# RH001_1.net
KiCad netlist of a schematic drawn in EAGLE
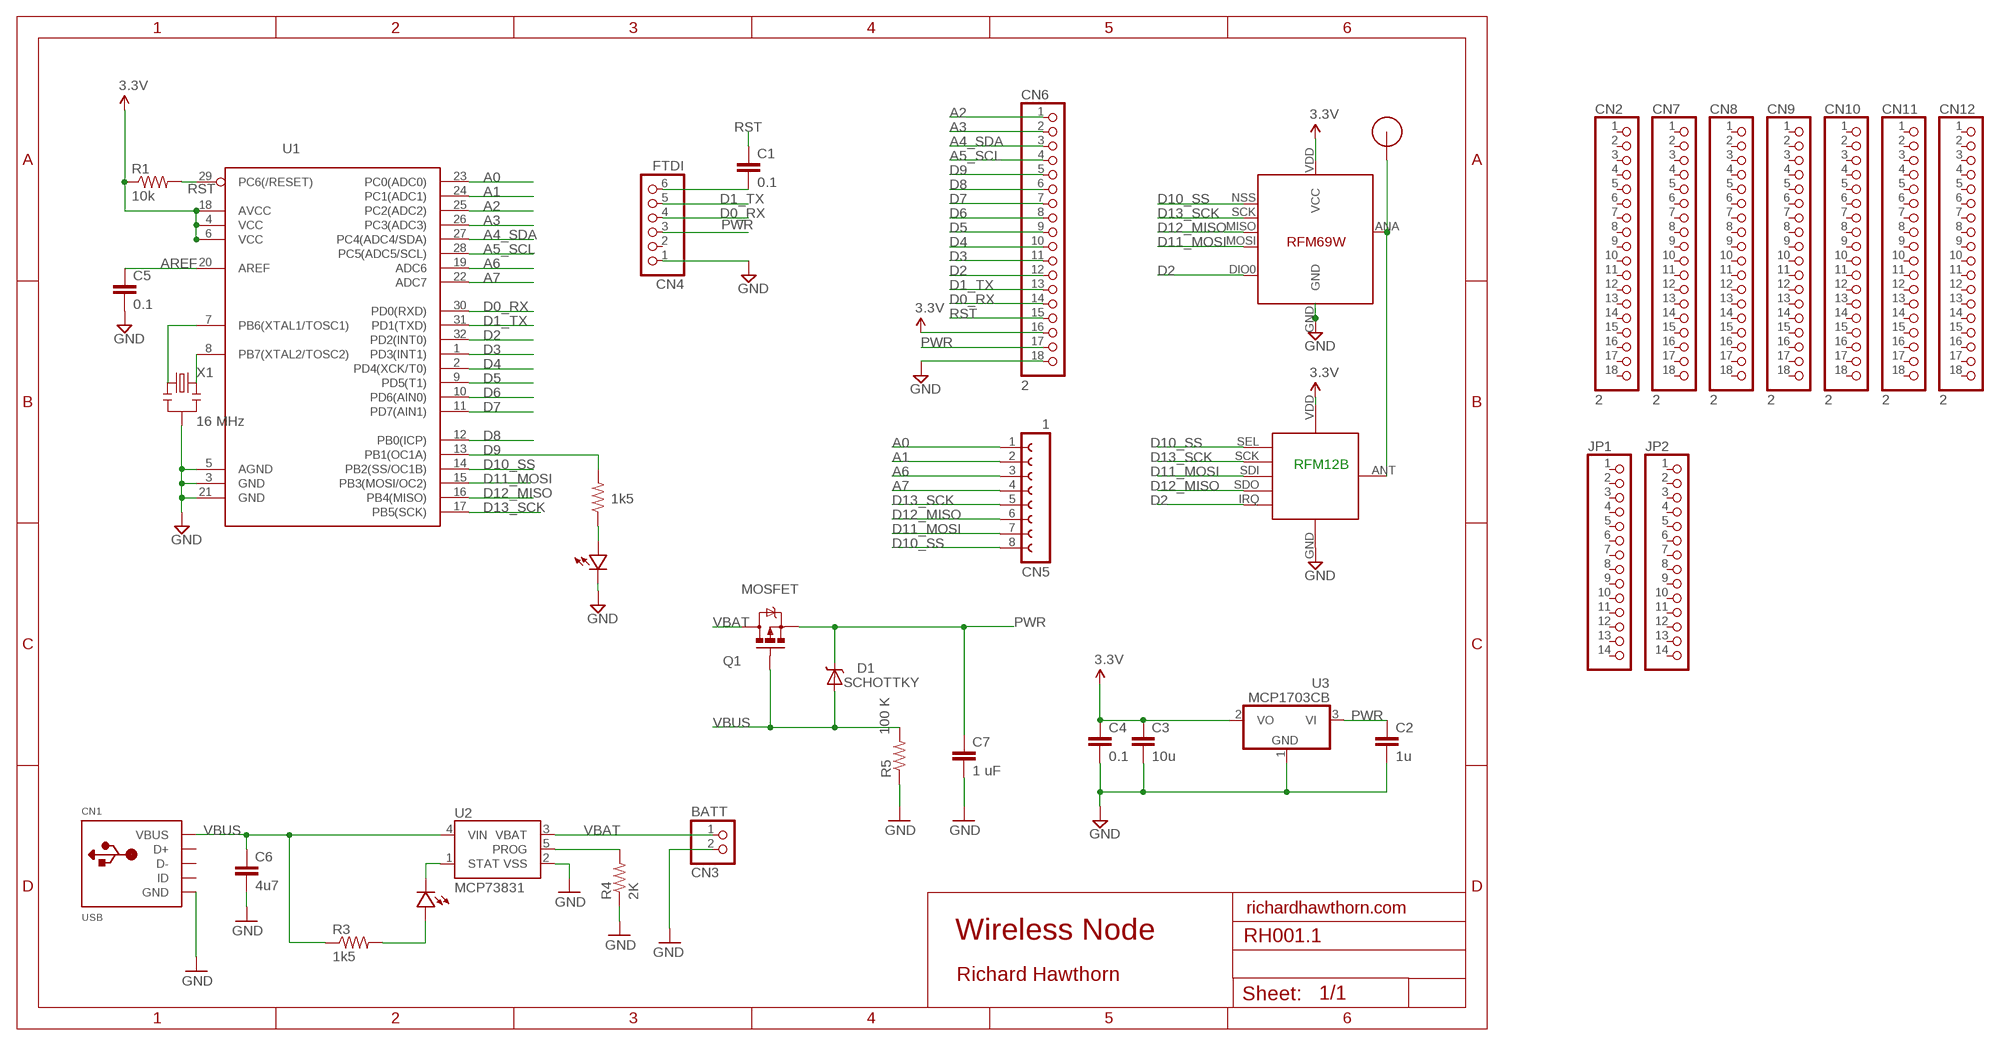
[diagram p0: schematic, sheet 1]

(export (version "E")
  (design (tool "Eeschema 10.0.6"))
  (components
    (comp (ref "C1")
      (value "0.1")
      (footprint "eagle-import:0603-CAP")
      (libsource (lib "eagle-import") (part "CAP0603-CAP"))
    )
    (comp (ref "C2")
      (value "1u")
      (footprint "eagle-import:0603-CAP")
      (libsource (lib "eagle-import") (part "CAP0603-CAP"))
    )
    (comp (ref "C3")
      (value "10u")
      (footprint "eagle-import:0805-CAP")
      (libsource (lib "eagle-import") (part "CAP0805-CAP"))
    )
    (comp (ref "C4")
      (value "0.1")
      (footprint "eagle-import:0603-CAP")
      (libsource (lib "eagle-import") (part "CAP0603-CAP"))
    )
    (comp (ref "C5")
      (value "0.1")
      (footprint "eagle-import:0603-CAP")
      (libsource (lib "eagle-import") (part "CAP0603-CAP"))
    )
    (comp (ref "C6")
      (value "4u7")
      (footprint "eagle-import:0603-CAP")
      (libsource (lib "eagle-import") (part "SparkFun_CAP0603-CAP"))
    )
    (comp (ref "C7")
      (value "1 uF")
      (footprint "eagle-import:0805")
      (libsource (lib "eagle-import") (part "SparkFun-Capacitors_CAP0805"))
    )
    (comp (ref "CN1")
      (value "USB")
      (footprint "eagle-import:USB-MINIB")
      (libsource (lib "eagle-import") (part "USBMINIB"))
    )
    (comp (ref "CN2")
      (value "2")
      (footprint "eagle-import:1X18")
      (libsource (lib "eagle-import") (part "PINHD-1X18"))
    )
    (comp (ref "CN3")
      (value "BATT")
      (footprint "eagle-import:JST-PH-2-SMT-RA")
      (libsource (lib "eagle-import") (part "JST_2PIN-SMT-RA"))
    )
    (comp (ref "CN4")
      (value "FTDI")
      (footprint "eagle-import:1X06")
      (libsource (lib "eagle-import") (part "PINHD-1X6"))
    )
    (comp (ref "CN5")
      (value "1")
      (footprint "eagle-import:FE08")
      (libsource (lib "eagle-import") (part "FE08-1"))
    )
    (comp (ref "CN6")
      (value "2")
      (footprint "eagle-import:1X18")
      (libsource (lib "eagle-import") (part "PINHD-1X18"))
    )
    (comp (ref "CN7")
      (value "2")
      (footprint "eagle-import:1X18")
      (libsource (lib "eagle-import") (part "PINHD-1X18"))
    )
    (comp (ref "CN8")
      (value "2")
      (footprint "eagle-import:1X18")
      (libsource (lib "eagle-import") (part "PINHD-1X18"))
    )
    (comp (ref "CN9")
      (value "2")
      (footprint "eagle-import:1X18")
      (libsource (lib "eagle-import") (part "PINHD-1X18"))
    )
    (comp (ref "CN10")
      (value "2")
      (footprint "eagle-import:1X18")
      (libsource (lib "eagle-import") (part "PINHD-1X18"))
    )
    (comp (ref "CN11")
      (value "2")
      (footprint "eagle-import:1X18")
      (libsource (lib "eagle-import") (part "PINHD-1X18"))
    )
    (comp (ref "CN12")
      (value "2")
      (footprint "eagle-import:1X18")
      (libsource (lib "eagle-import") (part "PINHD-1X18"))
    )
    (comp (ref "D1")
      (value "SCHOTTKY")
      (footprint "eagle-import:SMA-DIODE")
      (libsource (lib "eagle-import") (part "DIODE-SCHOTTKY_"))
    )
    (comp (ref "JP1")
      (value "PINHD-1X14")
      (footprint "eagle-import:1X14")
      (libsource (lib "eagle-import") (part "PINHD-1X14"))
    )
    (comp (ref "JP2")
      (value "PINHD-1X14")
      (footprint "eagle-import:1X14")
      (libsource (lib "eagle-import") (part "PINHD-1X14"))
    )
    (comp (ref "LED1")
      (value "LED0603")
      (footprint "eagle-import:0603-LED")
      (libsource (lib "eagle-import") (part "LED0603"))
    )
    (comp (ref "LED2")
      (value "LED0603")
      (footprint "eagle-import:0603-LED")
      (libsource (lib "eagle-import") (part "LED0603"))
    )
    (comp (ref "Q1")
      (value "MOSFET")
      (footprint "eagle-import:SOT23-3")
      (libsource (lib "eagle-import") (part "MOSFET-PCHANNELSMD"))
    )
    (comp (ref "R1")
      (value "10k")
      (footprint "eagle-import:0603-RES")
      (libsource (lib "eagle-import") (part "RESISTOR0603-RES"))
    )
    (comp (ref "R2")
      (value "1k5")
      (footprint "eagle-import:0603-RES")
      (libsource (lib "eagle-import") (part "RESISTOR0603-RES"))
    )
    (comp (ref "R3")
      (value "1k5")
      (footprint "eagle-import:0603-RES")
      (libsource (lib "eagle-import") (part "RESISTOR0603-RES"))
    )
    (comp (ref "R4")
      (value "2K")
      (footprint "eagle-import:0603-RES")
      (libsource (lib "eagle-import") (part "RESISTOR0603-RES"))
    )
    (comp (ref "R5")
      (value "100 K")
      (footprint "eagle-import:0805")
      (libsource (lib "eagle-import") (part "SparkFun-Resistors_RESISTOR0805-RES"))
    )
    (comp (ref "RF1")
      (value "RFM12B")
      (footprint "eagle-import:RFM12B-MINPADS")
      (libsource (lib "eagle-import") (part "RFM12B_MINPADS"))
    )
    (comp (ref "RF2")
      (value "RFM69")
      (footprint "eagle-import:RFM69W-MINPADS")
      (libsource (lib "eagle-import") (part "RFM69"))
    )
    (comp (ref "U$1")
      (value "RFM12B_ANTENNA")
      (footprint "eagle-import:RFM12B-ANTENNA")
      (libsource (lib "eagle-import") (part "RFM12B_ANTENNA"))
    )
    (comp (ref "U1")
      (value "ATMega-328")
      (footprint "eagle-import:TQFP32-08")
      (libsource (lib "eagle-import") (part "ATMEGA168/328TQFP32"))
    )
    (comp (ref "U2")
      (value "MCP73831")
      (footprint "eagle-import:SOT23-5")
      (libsource (lib "eagle-import") (part "MCP73831"))
    )
    (comp (ref "U3")
      (value "MCP1703CB")
      (footprint "eagle-import:SOT23")
      (libsource (lib "eagle-import") (part "MCP1703CB"))
    )
    (comp (ref "X1")
      (value "16 MHz")
      (footprint "eagle-import:RESONATOR-SMD")
      (libsource (lib "eagle-import") (part "RESONATORSMD"))
    )
  )
  (nets
    (net (code "1") (name "/A0") (class "Default")
      (node (ref "CN5") (pin "1") (pinfunction "1_1") (pintype "passive"))
      (node (ref "U1") (pin "23") (pinfunction "PC0(ADC0)_23") (pintype "bidirectional"))
    )
    (net (code "2") (name "/A1") (class "Default")
      (node (ref "CN5") (pin "2") (pinfunction "2_2") (pintype "passive"))
      (node (ref "U1") (pin "24") (pinfunction "PC1(ADC1)_24") (pintype "bidirectional"))
    )
    (net (code "3") (name "/A2") (class "Default")
      (node (ref "CN6") (pin "1") (pinfunction "1_1") (pintype "passive"))
      (node (ref "U1") (pin "25") (pinfunction "PC2(ADC2)_25") (pintype "bidirectional"))
    )
    (net (code "4") (name "/A3") (class "Default")
      (node (ref "CN6") (pin "2") (pinfunction "2_2") (pintype "passive"))
      (node (ref "U1") (pin "26") (pinfunction "PC3(ADC3)_26") (pintype "bidirectional"))
    )
    (net (code "5") (name "/A4_SDA") (class "Default")
      (node (ref "CN6") (pin "3") (pinfunction "3_3") (pintype "passive"))
      (node (ref "U1") (pin "27") (pinfunction "PC4(ADC4/SDA)_27") (pintype "bidirectional"))
    )
    (net (code "6") (name "/A5_SCL") (class "Default")
      (node (ref "CN6") (pin "4") (pinfunction "4_4") (pintype "passive"))
      (node (ref "U1") (pin "28") (pinfunction "PC5(ADC5/SCL)_28") (pintype "bidirectional"))
    )
    (net (code "7") (name "/A6") (class "Default")
      (node (ref "CN5") (pin "3") (pinfunction "3_3") (pintype "passive"))
      (node (ref "U1") (pin "19") (pinfunction "ADC6_19") (pintype "bidirectional"))
    )
    (net (code "8") (name "/A7") (class "Default")
      (node (ref "CN5") (pin "4") (pinfunction "4_4") (pintype "passive"))
      (node (ref "U1") (pin "22") (pinfunction "ADC7_22") (pintype "bidirectional"))
    )
    (net (code "9") (name "/AREF") (class "Default")
      (node (ref "C5") (pin "1") (pinfunction "1_1") (pintype "passive"))
      (node (ref "U1") (pin "20") (pinfunction "AREF_20") (pintype "bidirectional"))
    )
    (net (code "10") (name "/D0_RX") (class "Default")
      (node (ref "CN4") (pin "4") (pinfunction "4_4") (pintype "passive"))
      (node (ref "CN6") (pin "14") (pinfunction "14_14") (pintype "passive"))
      (node (ref "U1") (pin "30") (pinfunction "PD0(RXD)_30") (pintype "bidirectional"))
    )
    (net (code "11") (name "/D1_TX") (class "Default")
      (node (ref "CN4") (pin "5") (pinfunction "5_5") (pintype "passive"))
      (node (ref "CN6") (pin "13") (pinfunction "13_13") (pintype "passive"))
      (node (ref "U1") (pin "31") (pinfunction "PD1(TXD)_31") (pintype "bidirectional"))
    )
    (net (code "12") (name "/D2") (class "Default")
      (node (ref "CN6") (pin "12") (pinfunction "12_12") (pintype "passive"))
      (node (ref "RF1") (pin "IRQ") (pinfunction "IRQ_IRQ") (pintype "bidirectional"))
      (node (ref "RF2") (pin "DIO0") (pinfunction "DIO0_DIO0") (pintype "open_collector"))
      (node (ref "U1") (pin "32") (pinfunction "PD2(INT0)_32") (pintype "bidirectional"))
    )
    (net (code "13") (name "/D3") (class "Default")
      (node (ref "CN6") (pin "11") (pinfunction "11_11") (pintype "passive"))
      (node (ref "U1") (pin "1") (pinfunction "PD3(INT1)_1") (pintype "bidirectional"))
    )
    (net (code "14") (name "/D4") (class "Default")
      (node (ref "CN6") (pin "10") (pinfunction "10_10") (pintype "passive"))
      (node (ref "U1") (pin "2") (pinfunction "PD4(XCK/T0)_2") (pintype "bidirectional"))
    )
    (net (code "15") (name "/D5") (class "Default")
      (node (ref "CN6") (pin "9") (pinfunction "9_9") (pintype "passive"))
      (node (ref "U1") (pin "9") (pinfunction "PD5(T1)_9") (pintype "bidirectional"))
    )
    (net (code "16") (name "/D6") (class "Default")
      (node (ref "CN6") (pin "8") (pinfunction "8_8") (pintype "passive"))
      (node (ref "U1") (pin "10") (pinfunction "PD6(AIN0)_10") (pintype "bidirectional"))
    )
    (net (code "17") (name "/D7") (class "Default")
      (node (ref "CN6") (pin "7") (pinfunction "7_7") (pintype "passive"))
      (node (ref "U1") (pin "11") (pinfunction "PD7(AIN1)_11") (pintype "bidirectional"))
    )
    (net (code "18") (name "/D8") (class "Default")
      (node (ref "CN6") (pin "6") (pinfunction "6_6") (pintype "passive"))
      (node (ref "U1") (pin "12") (pinfunction "PB0(ICP)_12") (pintype "bidirectional"))
    )
    (net (code "19") (name "/D9") (class "Default")
      (node (ref "CN6") (pin "5") (pinfunction "5_5") (pintype "passive"))
      (node (ref "R2") (pin "2") (pinfunction "2_2") (pintype "passive"))
      (node (ref "U1") (pin "13") (pinfunction "PB1(OC1A)_13") (pintype "bidirectional"))
    )
    (net (code "20") (name "/D10_SS") (class "Default")
      (node (ref "CN5") (pin "8") (pinfunction "8_8") (pintype "passive"))
      (node (ref "RF1") (pin "SEL") (pinfunction "SEL_SEL") (pintype "bidirectional"))
      (node (ref "RF2") (pin "NSS") (pinfunction "SEL_NSS") (pintype "input"))
      (node (ref "U1") (pin "14") (pinfunction "PB2(SS/OC1B)_14") (pintype "bidirectional"))
    )
    (net (code "21") (name "/D11_MOSI") (class "Default")
      (node (ref "CN5") (pin "7") (pinfunction "7_7") (pintype "passive"))
      (node (ref "RF1") (pin "SDI") (pinfunction "SDI/MOSI_SDI") (pintype "bidirectional"))
      (node (ref "RF2") (pin "MOSI") (pinfunction "MOSI_MOSI") (pintype "output"))
      (node (ref "U1") (pin "15") (pinfunction "PB3(MOSI/OC2)_15") (pintype "bidirectional"))
    )
    (net (code "22") (name "/D12_MISO") (class "Default")
      (node (ref "CN5") (pin "6") (pinfunction "6_6") (pintype "passive"))
      (node (ref "RF1") (pin "SDO") (pinfunction "SDO/MISO_SDO") (pintype "bidirectional"))
      (node (ref "RF2") (pin "MISO") (pinfunction "MISO_MISO") (pintype "input"))
      (node (ref "U1") (pin "16") (pinfunction "PB4(MISO)_16") (pintype "bidirectional"))
    )
    (net (code "23") (name "/D13_SCK") (class "Default")
      (node (ref "CN5") (pin "5") (pinfunction "5_5") (pintype "passive"))
      (node (ref "RF1") (pin "SCK") (pinfunction "SCK_SCK") (pintype "bidirectional"))
      (node (ref "RF2") (pin "SCK") (pinfunction "SCK_SCK") (pintype "input"))
      (node (ref "U1") (pin "17") (pinfunction "PB5(SCK)_17") (pintype "bidirectional"))
    )
    (net (code "24") (name "/PWR") (class "Default")
      (node (ref "C2") (pin "1") (pinfunction "1_1") (pintype "passive"))
      (node (ref "C7") (pin "1") (pinfunction "1_1") (pintype "passive"))
      (node (ref "CN4") (pin "3") (pinfunction "3_3") (pintype "passive"))
      (node (ref "CN6") (pin "17") (pinfunction "17_17") (pintype "passive"))
      (node (ref "D1") (pin "C") (pinfunction "C_C") (pintype "passive"))
      (node (ref "Q1") (pin "2") (pinfunction "S_2") (pintype "passive"))
      (node (ref "U3") (pin "3") (pinfunction "VI_3") (pintype "input"))
    )
    (net (code "25") (name "/RST") (class "Default")
      (node (ref "C1") (pin "1") (pinfunction "1_1") (pintype "passive"))
      (node (ref "CN6") (pin "15") (pinfunction "15_15") (pintype "passive"))
      (node (ref "R1") (pin "2") (pinfunction "2_2") (pintype "passive"))
      (node (ref "U1") (pin "29") (pinfunction "PC6(/RESET)_29") (pintype "bidirectional"))
    )
    (net (code "26") (name "/VBAT") (class "Default")
      (node (ref "CN3") (pin "1") (pinfunction "2_1") (pintype "passive"))
      (node (ref "Q1") (pin "3") (pinfunction "D_3") (pintype "passive"))
      (node (ref "U2") (pin "3") (pinfunction "VBAT_3") (pintype "power_in"))
    )
    (net (code "27") (name "/VBUS") (class "Default")
      (node (ref "C6") (pin "1") (pinfunction "1_1") (pintype "passive"))
      (node (ref "CN1") (pin "VBUS") (pinfunction "VBUS_VBUS") (pintype "power_in"))
      (node (ref "D1") (pin "A") (pinfunction "A_A") (pintype "passive"))
      (node (ref "Q1") (pin "1") (pinfunction "G_1") (pintype "passive"))
      (node (ref "R3") (pin "1") (pinfunction "1_1") (pintype "passive"))
      (node (ref "R5") (pin "2") (pinfunction "2_2") (pintype "passive"))
      (node (ref "U2") (pin "4") (pinfunction "VIN_4") (pintype "power_in"))
    )
    (net (code "28") (name "3.3V") (class "Default")
      (node (ref "C3") (pin "1") (pinfunction "1_1") (pintype "passive"))
      (node (ref "C4") (pin "1") (pinfunction "1_1") (pintype "passive"))
      (node (ref "CN6") (pin "16") (pinfunction "16_16") (pintype "passive"))
      (node (ref "R1") (pin "1") (pinfunction "1_1") (pintype "passive"))
      (node (ref "RF1") (pin "VDD") (pinfunction "VDD_VDD") (pintype "bidirectional"))
      (node (ref "RF2") (pin "VDD") (pinfunction "VCC_VDD") (pintype "power_in"))
      (node (ref "U1") (pin "18") (pinfunction "AVCC_18") (pintype "bidirectional"))
      (node (ref "U1") (pin "4") (pinfunction "VCC_4") (pintype "bidirectional"))
      (node (ref "U1") (pin "6") (pinfunction "VCC_6") (pintype "bidirectional"))
      (node (ref "U3") (pin "2") (pinfunction "VO_2") (pintype "passive"))
    )
    (net (code "29") (name "GND") (class "Default")
      (node (ref "C2") (pin "2") (pinfunction "2_2") (pintype "passive"))
      (node (ref "C3") (pin "2") (pinfunction "2_2") (pintype "passive"))
      (node (ref "C4") (pin "2") (pinfunction "2_2") (pintype "passive"))
      (node (ref "C5") (pin "2") (pinfunction "2_2") (pintype "passive"))
      (node (ref "C6") (pin "2") (pinfunction "2_2") (pintype "passive"))
      (node (ref "C7") (pin "2") (pinfunction "2_2") (pintype "passive"))
      (node (ref "CN1") (pin "GND") (pinfunction "GND_GND") (pintype "power_in"))
      (node (ref "CN3") (pin "2") (pinfunction "1_2") (pintype "passive"))
      (node (ref "CN4") (pin "1") (pinfunction "1_1") (pintype "passive"))
      (node (ref "CN6") (pin "18") (pinfunction "18_18") (pintype "passive"))
      (node (ref "LED2") (pin "MINUS") (pinfunction "MINUS_MINUS") (pintype "passive"))
      (node (ref "R4") (pin "1") (pinfunction "1_1") (pintype "passive"))
      (node (ref "R5") (pin "1") (pinfunction "1_1") (pintype "passive"))
      (node (ref "RF1") (pin "GND") (pinfunction "GND_GND") (pintype "bidirectional"))
      (node (ref "RF2") (pin "GND") (pinfunction "GND_GND") (pintype "power_in"))
      (node (ref "U1") (pin "21") (pinfunction "GND_21") (pintype "bidirectional"))
      (node (ref "U1") (pin "3") (pinfunction "GND_3") (pintype "bidirectional"))
      (node (ref "U1") (pin "5") (pinfunction "AGND_5") (pintype "bidirectional"))
      (node (ref "U2") (pin "2") (pinfunction "VSS_2") (pintype "power_in"))
      (node (ref "U3") (pin "1") (pinfunction "GND_1") (pintype "passive"))
      (node (ref "X1") (pin "2") (pinfunction "2_2") (pintype "passive"))
    )
    (net (code "30") (name "Net-(C1-Pad2)") (class "Default")
      (node (ref "C1") (pin "2") (pinfunction "2_2") (pintype "passive"))
      (node (ref "CN4") (pin "6") (pinfunction "6_6") (pintype "passive"))
    )
    (net (code "31") (name "Net-(LED1-PadPLUS)") (class "Default")
      (node (ref "LED1") (pin "PLUS") (pinfunction "PLUS_PLUS") (pintype "passive"))
      (node (ref "R3") (pin "2") (pinfunction "2_2") (pintype "passive"))
    )
    (net (code "32") (name "Net-(LED2-PadPLUS)") (class "Default")
      (node (ref "LED2") (pin "PLUS") (pinfunction "PLUS_PLUS") (pintype "passive"))
      (node (ref "R2") (pin "1") (pinfunction "1_1") (pintype "passive"))
    )
    (net (code "33") (name "Net-(RF2-ANT)") (class "Default")
      (node (ref "RF1") (pin "ANT") (pinfunction "ANT_ANT") (pintype "bidirectional"))
      (node (ref "RF2") (pin "ANA") (pinfunction "ANT_ANA") (pintype "passive"))
      (node (ref "U$1") (pin "P$1") (pinfunction "1_P$1") (pintype "bidirectional"))
    )
    (net (code "34") (name "Net-(U1-PB6(XTAL1{slash}TOSC1))") (class "Default")
      (node (ref "U1") (pin "7") (pinfunction "PB6(XTAL1/TOSC1)_7") (pintype "bidirectional"))
      (node (ref "X1") (pin "1") (pinfunction "1_1") (pintype "passive"))
    )
    (net (code "35") (name "Net-(U1-PB7(XTAL2{slash}TOSC2))") (class "Default")
      (node (ref "U1") (pin "8") (pinfunction "PB7(XTAL2/TOSC2)_8") (pintype "bidirectional"))
      (node (ref "X1") (pin "3") (pinfunction "3_3") (pintype "passive"))
    )
    (net (code "36") (name "Net-(U2-PROG)") (class "Default")
      (node (ref "R4") (pin "2") (pinfunction "2_2") (pintype "passive"))
      (node (ref "U2") (pin "5") (pinfunction "PROG_5") (pintype "input"))
    )
    (net (code "37") (name "Net-(U2-STAT)") (class "Default")
      (node (ref "LED1") (pin "MINUS") (pinfunction "MINUS_MINUS") (pintype "passive"))
      (node (ref "U2") (pin "1") (pinfunction "STAT_1") (pintype "output"))
    )
    (net (code "38") (name "unconnected-(CN1-PadD+)") (class "Default")
      (node (ref "CN1") (pin "D+") (pinfunction "D+_D+") (pintype "bidirectional"))
    )
    (net (code "39") (name "unconnected-(CN1-PadD-)") (class "Default")
      (node (ref "CN1") (pin "D-") (pinfunction "D-_D-") (pintype "bidirectional"))
    )
    (net (code "40") (name "unconnected-(CN1-PadID)") (class "Default")
      (node (ref "CN1") (pin "ID") (pinfunction "ID_ID") (pintype "bidirectional"))
    )
    (net (code "41") (name "unconnected-(CN2-Pad1)") (class "Default")
      (node (ref "CN2") (pin "1") (pinfunction "1_1") (pintype "passive"))
    )
    (net (code "42") (name "unconnected-(CN2-Pad2)") (class "Default")
      (node (ref "CN2") (pin "2") (pinfunction "2_2") (pintype "passive"))
    )
    (net (code "43") (name "unconnected-(CN2-Pad3)") (class "Default")
      (node (ref "CN2") (pin "3") (pinfunction "3_3") (pintype "passive"))
    )
    (net (code "44") (name "unconnected-(CN2-Pad4)") (class "Default")
      (node (ref "CN2") (pin "4") (pinfunction "4_4") (pintype "passive"))
    )
    (net (code "45") (name "unconnected-(CN2-Pad5)") (class "Default")
      (node (ref "CN2") (pin "5") (pinfunction "5_5") (pintype "passive"))
    )
    (net (code "46") (name "unconnected-(CN2-Pad6)") (class "Default")
      (node (ref "CN2") (pin "6") (pinfunction "6_6") (pintype "passive"))
    )
    (net (code "47") (name "unconnected-(CN2-Pad7)") (class "Default")
      (node (ref "CN2") (pin "7") (pinfunction "7_7") (pintype "passive"))
    )
    (net (code "48") (name "unconnected-(CN2-Pad8)") (class "Default")
      (node (ref "CN2") (pin "8") (pinfunction "8_8") (pintype "passive"))
    )
    (net (code "49") (name "unconnected-(CN2-Pad9)") (class "Default")
      (node (ref "CN2") (pin "9") (pinfunction "9_9") (pintype "passive"))
    )
    (net (code "50") (name "unconnected-(CN2-Pad10)") (class "Default")
      (node (ref "CN2") (pin "10") (pinfunction "10_10") (pintype "passive"))
    )
    (net (code "51") (name "unconnected-(CN2-Pad11)") (class "Default")
      (node (ref "CN2") (pin "11") (pinfunction "11_11") (pintype "passive"))
    )
    (net (code "52") (name "unconnected-(CN2-Pad12)") (class "Default")
      (node (ref "CN2") (pin "12") (pinfunction "12_12") (pintype "passive"))
    )
    (net (code "53") (name "unconnected-(CN2-Pad13)") (class "Default")
      (node (ref "CN2") (pin "13") (pinfunction "13_13") (pintype "passive"))
    )
    (net (code "54") (name "unconnected-(CN2-Pad14)") (class "Default")
      (node (ref "CN2") (pin "14") (pinfunction "14_14") (pintype "passive"))
    )
    (net (code "55") (name "unconnected-(CN2-Pad15)") (class "Default")
      (node (ref "CN2") (pin "15") (pinfunction "15_15") (pintype "passive"))
    )
    (net (code "56") (name "unconnected-(CN2-Pad16)") (class "Default")
      (node (ref "CN2") (pin "16") (pinfunction "16_16") (pintype "passive"))
    )
    (net (code "57") (name "unconnected-(CN2-Pad17)") (class "Default")
      (node (ref "CN2") (pin "17") (pinfunction "17_17") (pintype "passive"))
    )
    (net (code "58") (name "unconnected-(CN2-Pad18)") (class "Default")
      (node (ref "CN2") (pin "18") (pinfunction "18_18") (pintype "passive"))
    )
    (net (code "59") (name "unconnected-(CN4-Pad2)") (class "Default")
      (node (ref "CN4") (pin "2") (pinfunction "2_2") (pintype "passive"))
    )
    (net (code "60") (name "unconnected-(CN7-Pad1)") (class "Default")
      (node (ref "CN7") (pin "1") (pinfunction "1_1") (pintype "passive"))
    )
    (net (code "61") (name "unconnected-(CN7-Pad2)") (class "Default")
      (node (ref "CN7") (pin "2") (pinfunction "2_2") (pintype "passive"))
    )
    (net (code "62") (name "unconnected-(CN7-Pad3)") (class "Default")
      (node (ref "CN7") (pin "3") (pinfunction "3_3") (pintype "passive"))
    )
    (net (code "63") (name "unconnected-(CN7-Pad4)") (class "Default")
      (node (ref "CN7") (pin "4") (pinfunction "4_4") (pintype "passive"))
    )
    (net (code "64") (name "unconnected-(CN7-Pad5)") (class "Default")
      (node (ref "CN7") (pin "5") (pinfunction "5_5") (pintype "passive"))
    )
    (net (code "65") (name "unconnected-(CN7-Pad6)") (class "Default")
      (node (ref "CN7") (pin "6") (pinfunction "6_6") (pintype "passive"))
    )
    (net (code "66") (name "unconnected-(CN7-Pad7)") (class "Default")
      (node (ref "CN7") (pin "7") (pinfunction "7_7") (pintype "passive"))
    )
    (net (code "67") (name "unconnected-(CN7-Pad8)") (class "Default")
      (node (ref "CN7") (pin "8") (pinfunction "8_8") (pintype "passive"))
    )
    (net (code "68") (name "unconnected-(CN7-Pad9)") (class "Default")
      (node (ref "CN7") (pin "9") (pinfunction "9_9") (pintype "passive"))
    )
    (net (code "69") (name "unconnected-(CN7-Pad10)") (class "Default")
      (node (ref "CN7") (pin "10") (pinfunction "10_10") (pintype "passive"))
    )
    (net (code "70") (name "unconnected-(CN7-Pad11)") (class "Default")
      (node (ref "CN7") (pin "11") (pinfunction "11_11") (pintype "passive"))
    )
    (net (code "71") (name "unconnected-(CN7-Pad12)") (class "Default")
      (node (ref "CN7") (pin "12") (pinfunction "12_12") (pintype "passive"))
    )
    (net (code "72") (name "unconnected-(CN7-Pad13)") (class "Default")
      (node (ref "CN7") (pin "13") (pinfunction "13_13") (pintype "passive"))
    )
    (net (code "73") (name "unconnected-(CN7-Pad14)") (class "Default")
      (node (ref "CN7") (pin "14") (pinfunction "14_14") (pintype "passive"))
    )
    (net (code "74") (name "unconnected-(CN7-Pad15)") (class "Default")
      (node (ref "CN7") (pin "15") (pinfunction "15_15") (pintype "passive"))
    )
    (net (code "75") (name "unconnected-(CN7-Pad16)") (class "Default")
      (node (ref "CN7") (pin "16") (pinfunction "16_16") (pintype "passive"))
    )
    (net (code "76") (name "unconnected-(CN7-Pad17)") (class "Default")
      (node (ref "CN7") (pin "17") (pinfunction "17_17") (pintype "passive"))
    )
    (net (code "77") (name "unconnected-(CN7-Pad18)") (class "Default")
      (node (ref "CN7") (pin "18") (pinfunction "18_18") (pintype "passive"))
    )
    (net (code "78") (name "unconnected-(CN8-Pad1)") (class "Default")
      (node (ref "CN8") (pin "1") (pinfunction "1_1") (pintype "passive"))
    )
    (net (code "79") (name "unconnected-(CN8-Pad2)") (class "Default")
      (node (ref "CN8") (pin "2") (pinfunction "2_2") (pintype "passive"))
    )
    (net (code "80") (name "unconnected-(CN8-Pad3)") (class "Default")
      (node (ref "CN8") (pin "3") (pinfunction "3_3") (pintype "passive"))
    )
    (net (code "81") (name "unconnected-(CN8-Pad4)") (class "Default")
      (node (ref "CN8") (pin "4") (pinfunction "4_4") (pintype "passive"))
    )
    (net (code "82") (name "unconnected-(CN8-Pad5)") (class "Default")
      (node (ref "CN8") (pin "5") (pinfunction "5_5") (pintype "passive"))
    )
    (net (code "83") (name "unconnected-(CN8-Pad6)") (class "Default")
      (node (ref "CN8") (pin "6") (pinfunction "6_6") (pintype "passive"))
    )
    (net (code "84") (name "unconnected-(CN8-Pad7)") (class "Default")
      (node (ref "CN8") (pin "7") (pinfunction "7_7") (pintype "passive"))
    )
    (net (code "85") (name "unconnected-(CN8-Pad8)") (class "Default")
      (node (ref "CN8") (pin "8") (pinfunction "8_8") (pintype "passive"))
    )
    (net (code "86") (name "unconnected-(CN8-Pad9)") (class "Default")
      (node (ref "CN8") (pin "9") (pinfunction "9_9") (pintype "passive"))
    )
    (net (code "87") (name "unconnected-(CN8-Pad10)") (class "Default")
      (node (ref "CN8") (pin "10") (pinfunction "10_10") (pintype "passive"))
    )
    (net (code "88") (name "unconnected-(CN8-Pad11)") (class "Default")
      (node (ref "CN8") (pin "11") (pinfunction "11_11") (pintype "passive"))
    )
    (net (code "89") (name "unconnected-(CN8-Pad12)") (class "Default")
      (node (ref "CN8") (pin "12") (pinfunction "12_12") (pintype "passive"))
    )
    (net (code "90") (name "unconnected-(CN8-Pad13)") (class "Default")
      (node (ref "CN8") (pin "13") (pinfunction "13_13") (pintype "passive"))
    )
    (net (code "91") (name "unconnected-(CN8-Pad14)") (class "Default")
      (node (ref "CN8") (pin "14") (pinfunction "14_14") (pintype "passive"))
    )
    (net (code "92") (name "unconnected-(CN8-Pad15)") (class "Default")
      (node (ref "CN8") (pin "15") (pinfunction "15_15") (pintype "passive"))
    )
    (net (code "93") (name "unconnected-(CN8-Pad16)") (class "Default")
      (node (ref "CN8") (pin "16") (pinfunction "16_16") (pintype "passive"))
    )
    (net (code "94") (name "unconnected-(CN8-Pad17)") (class "Default")
      (node (ref "CN8") (pin "17") (pinfunction "17_17") (pintype "passive"))
    )
    (net (code "95") (name "unconnected-(CN8-Pad18)") (class "Default")
      (node (ref "CN8") (pin "18") (pinfunction "18_18") (pintype "passive"))
    )
    (net (code "96") (name "unconnected-(CN9-Pad1)") (class "Default")
      (node (ref "CN9") (pin "1") (pinfunction "1_1") (pintype "passive"))
    )
    (net (code "97") (name "unconnected-(CN9-Pad2)") (class "Default")
      (node (ref "CN9") (pin "2") (pinfunction "2_2") (pintype "passive"))
    )
    (net (code "98") (name "unconnected-(CN9-Pad3)") (class "Default")
      (node (ref "CN9") (pin "3") (pinfunction "3_3") (pintype "passive"))
    )
    (net (code "99") (name "unconnected-(CN9-Pad4)") (class "Default")
      (node (ref "CN9") (pin "4") (pinfunction "4_4") (pintype "passive"))
    )
    (net (code "100") (name "unconnected-(CN9-Pad5)") (class "Default")
      (node (ref "CN9") (pin "5") (pinfunction "5_5") (pintype "passive"))
    )
    (net (code "101") (name "unconnected-(CN9-Pad6)") (class "Default")
      (node (ref "CN9") (pin "6") (pinfunction "6_6") (pintype "passive"))
    )
    (net (code "102") (name "unconnected-(CN9-Pad7)") (class "Default")
      (node (ref "CN9") (pin "7") (pinfunction "7_7") (pintype "passive"))
    )
    (net (code "103") (name "unconnected-(CN9-Pad8)") (class "Default")
      (node (ref "CN9") (pin "8") (pinfunction "8_8") (pintype "passive"))
    )
    (net (code "104") (name "unconnected-(CN9-Pad9)") (class "Default")
      (node (ref "CN9") (pin "9") (pinfunction "9_9") (pintype "passive"))
    )
    (net (code "105") (name "unconnected-(CN9-Pad10)") (class "Default")
      (node (ref "CN9") (pin "10") (pinfunction "10_10") (pintype "passive"))
    )
    (net (code "106") (name "unconnected-(CN9-Pad11)") (class "Default")
      (node (ref "CN9") (pin "11") (pinfunction "11_11") (pintype "passive"))
    )
    (net (code "107") (name "unconnected-(CN9-Pad12)") (class "Default")
      (node (ref "CN9") (pin "12") (pinfunction "12_12") (pintype "passive"))
    )
    (net (code "108") (name "unconnected-(CN9-Pad13)") (class "Default")
      (node (ref "CN9") (pin "13") (pinfunction "13_13") (pintype "passive"))
    )
    (net (code "109") (name "unconnected-(CN9-Pad14)") (class "Default")
      (node (ref "CN9") (pin "14") (pinfunction "14_14") (pintype "passive"))
    )
    (net (code "110") (name "unconnected-(CN9-Pad15)") (class "Default")
      (node (ref "CN9") (pin "15") (pinfunction "15_15") (pintype "passive"))
    )
    (net (code "111") (name "unconnected-(CN9-Pad16)") (class "Default")
      (node (ref "CN9") (pin "16") (pinfunction "16_16") (pintype "passive"))
    )
    (net (code "112") (name "unconnected-(CN9-Pad17)") (class "Default")
      (node (ref "CN9") (pin "17") (pinfunction "17_17") (pintype "passive"))
    )
    (net (code "113") (name "unconnected-(CN9-Pad18)") (class "Default")
      (node (ref "CN9") (pin "18") (pinfunction "18_18") (pintype "passive"))
    )
    (net (code "114") (name "unconnected-(CN10-Pad1)") (class "Default")
      (node (ref "CN10") (pin "1") (pinfunction "1_1") (pintype "passive"))
    )
    (net (code "115") (name "unconnected-(CN10-Pad2)") (class "Default")
      (node (ref "CN10") (pin "2") (pinfunction "2_2") (pintype "passive"))
    )
    (net (code "116") (name "unconnected-(CN10-Pad3)") (class "Default")
      (node (ref "CN10") (pin "3") (pinfunction "3_3") (pintype "passive"))
    )
    (net (code "117") (name "unconnected-(CN10-Pad4)") (class "Default")
      (node (ref "CN10") (pin "4") (pinfunction "4_4") (pintype "passive"))
    )
    (net (code "118") (name "unconnected-(CN10-Pad5)") (class "Default")
      (node (ref "CN10") (pin "5") (pinfunction "5_5") (pintype "passive"))
    )
    (net (code "119") (name "unconnected-(CN10-Pad6)") (class "Default")
      (node (ref "CN10") (pin "6") (pinfunction "6_6") (pintype "passive"))
    )
    (net (code "120") (name "unconnected-(CN10-Pad7)") (class "Default")
      (node (ref "CN10") (pin "7") (pinfunction "7_7") (pintype "passive"))
    )
    (net (code "121") (name "unconnected-(CN10-Pad8)") (class "Default")
      (node (ref "CN10") (pin "8") (pinfunction "8_8") (pintype "passive"))
    )
    (net (code "122") (name "unconnected-(CN10-Pad9)") (class "Default")
      (node (ref "CN10") (pin "9") (pinfunction "9_9") (pintype "passive"))
    )
    (net (code "123") (name "unconnected-(CN10-Pad10)") (class "Default")
      (node (ref "CN10") (pin "10") (pinfunction "10_10") (pintype "passive"))
    )
    (net (code "124") (name "unconnected-(CN10-Pad11)") (class "Default")
      (node (ref "CN10") (pin "11") (pinfunction "11_11") (pintype "passive"))
    )
    (net (code "125") (name "unconnected-(CN10-Pad12)") (class "Default")
      (node (ref "CN10") (pin "12") (pinfunction "12_12") (pintype "passive"))
    )
    (net (code "126") (name "unconnected-(CN10-Pad13)") (class "Default")
      (node (ref "CN10") (pin "13") (pinfunction "13_13") (pintype "passive"))
    )
    (net (code "127") (name "unconnected-(CN10-Pad14)") (class "Default")
      (node (ref "CN10") (pin "14") (pinfunction "14_14") (pintype "passive"))
    )
    (net (code "128") (name "unconnected-(CN10-Pad15)") (class "Default")
      (node (ref "CN10") (pin "15") (pinfunction "15_15") (pintype "passive"))
    )
    (net (code "129") (name "unconnected-(CN10-Pad16)") (class "Default")
      (node (ref "CN10") (pin "16") (pinfunction "16_16") (pintype "passive"))
    )
    (net (code "130") (name "unconnected-(CN10-Pad17)") (class "Default")
      (node (ref "CN10") (pin "17") (pinfunction "17_17") (pintype "passive"))
    )
    (net (code "131") (name "unconnected-(CN10-Pad18)") (class "Default")
      (node (ref "CN10") (pin "18") (pinfunction "18_18") (pintype "passive"))
    )
    (net (code "132") (name "unconnected-(CN11-Pad1)") (class "Default")
      (node (ref "CN11") (pin "1") (pinfunction "1_1") (pintype "passive"))
    )
    (net (code "133") (name "unconnected-(CN11-Pad2)") (class "Default")
      (node (ref "CN11") (pin "2") (pinfunction "2_2") (pintype "passive"))
    )
    (net (code "134") (name "unconnected-(CN11-Pad3)") (class "Default")
      (node (ref "CN11") (pin "3") (pinfunction "3_3") (pintype "passive"))
    )
    (net (code "135") (name "unconnected-(CN11-Pad4)") (class "Default")
      (node (ref "CN11") (pin "4") (pinfunction "4_4") (pintype "passive"))
    )
    (net (code "136") (name "unconnected-(CN11-Pad5)") (class "Default")
      (node (ref "CN11") (pin "5") (pinfunction "5_5") (pintype "passive"))
    )
    (net (code "137") (name "unconnected-(CN11-Pad6)") (class "Default")
      (node (ref "CN11") (pin "6") (pinfunction "6_6") (pintype "passive"))
    )
    (net (code "138") (name "unconnected-(CN11-Pad7)") (class "Default")
      (node (ref "CN11") (pin "7") (pinfunction "7_7") (pintype "passive"))
    )
    (net (code "139") (name "unconnected-(CN11-Pad8)") (class "Default")
      (node (ref "CN11") (pin "8") (pinfunction "8_8") (pintype "passive"))
    )
    (net (code "140") (name "unconnected-(CN11-Pad9)") (class "Default")
      (node (ref "CN11") (pin "9") (pinfunction "9_9") (pintype "passive"))
    )
    (net (code "141") (name "unconnected-(CN11-Pad10)") (class "Default")
      (node (ref "CN11") (pin "10") (pinfunction "10_10") (pintype "passive"))
    )
    (net (code "142") (name "unconnected-(CN11-Pad11)") (class "Default")
      (node (ref "CN11") (pin "11") (pinfunction "11_11") (pintype "passive"))
    )
    (net (code "143") (name "unconnected-(CN11-Pad12)") (class "Default")
      (node (ref "CN11") (pin "12") (pinfunction "12_12") (pintype "passive"))
    )
    (net (code "144") (name "unconnected-(CN11-Pad13)") (class "Default")
      (node (ref "CN11") (pin "13") (pinfunction "13_13") (pintype "passive"))
    )
    (net (code "145") (name "unconnected-(CN11-Pad14)") (class "Default")
      (node (ref "CN11") (pin "14") (pinfunction "14_14") (pintype "passive"))
    )
    (net (code "146") (name "unconnected-(CN11-Pad15)") (class "Default")
      (node (ref "CN11") (pin "15") (pinfunction "15_15") (pintype "passive"))
    )
    (net (code "147") (name "unconnected-(CN11-Pad16)") (class "Default")
      (node (ref "CN11") (pin "16") (pinfunction "16_16") (pintype "passive"))
    )
    (net (code "148") (name "unconnected-(CN11-Pad17)") (class "Default")
      (node (ref "CN11") (pin "17") (pinfunction "17_17") (pintype "passive"))
    )
    (net (code "149") (name "unconnected-(CN11-Pad18)") (class "Default")
      (node (ref "CN11") (pin "18") (pinfunction "18_18") (pintype "passive"))
    )
    (net (code "150") (name "unconnected-(CN12-Pad1)") (class "Default")
      (node (ref "CN12") (pin "1") (pinfunction "1_1") (pintype "passive"))
    )
    (net (code "151") (name "unconnected-(CN12-Pad2)") (class "Default")
      (node (ref "CN12") (pin "2") (pinfunction "2_2") (pintype "passive"))
    )
    (net (code "152") (name "unconnected-(CN12-Pad3)") (class "Default")
      (node (ref "CN12") (pin "3") (pinfunction "3_3") (pintype "passive"))
    )
    (net (code "153") (name "unconnected-(CN12-Pad4)") (class "Default")
      (node (ref "CN12") (pin "4") (pinfunction "4_4") (pintype "passive"))
    )
    (net (code "154") (name "unconnected-(CN12-Pad5)") (class "Default")
      (node (ref "CN12") (pin "5") (pinfunction "5_5") (pintype "passive"))
    )
    (net (code "155") (name "unconnected-(CN12-Pad6)") (class "Default")
      (node (ref "CN12") (pin "6") (pinfunction "6_6") (pintype "passive"))
    )
    (net (code "156") (name "unconnected-(CN12-Pad7)") (class "Default")
      (node (ref "CN12") (pin "7") (pinfunction "7_7") (pintype "passive"))
    )
    (net (code "157") (name "unconnected-(CN12-Pad8)") (class "Default")
      (node (ref "CN12") (pin "8") (pinfunction "8_8") (pintype "passive"))
    )
    (net (code "158") (name "unconnected-(CN12-Pad9)") (class "Default")
      (node (ref "CN12") (pin "9") (pinfunction "9_9") (pintype "passive"))
    )
    (net (code "159") (name "unconnected-(CN12-Pad10)") (class "Default")
      (node (ref "CN12") (pin "10") (pinfunction "10_10") (pintype "passive"))
    )
    (net (code "160") (name "unconnected-(CN12-Pad11)") (class "Default")
      (node (ref "CN12") (pin "11") (pinfunction "11_11") (pintype "passive"))
    )
    (net (code "161") (name "unconnected-(CN12-Pad12)") (class "Default")
      (node (ref "CN12") (pin "12") (pinfunction "12_12") (pintype "passive"))
    )
    (net (code "162") (name "unconnected-(CN12-Pad13)") (class "Default")
      (node (ref "CN12") (pin "13") (pinfunction "13_13") (pintype "passive"))
    )
    (net (code "163") (name "unconnected-(CN12-Pad14)") (class "Default")
      (node (ref "CN12") (pin "14") (pinfunction "14_14") (pintype "passive"))
    )
    (net (code "164") (name "unconnected-(CN12-Pad15)") (class "Default")
      (node (ref "CN12") (pin "15") (pinfunction "15_15") (pintype "passive"))
    )
    (net (code "165") (name "unconnected-(CN12-Pad16)") (class "Default")
      (node (ref "CN12") (pin "16") (pinfunction "16_16") (pintype "passive"))
    )
    (net (code "166") (name "unconnected-(CN12-Pad17)") (class "Default")
      (node (ref "CN12") (pin "17") (pinfunction "17_17") (pintype "passive"))
    )
    (net (code "167") (name "unconnected-(CN12-Pad18)") (class "Default")
      (node (ref "CN12") (pin "18") (pinfunction "18_18") (pintype "passive"))
    )
    (net (code "168") (name "unconnected-(JP1-Pad1)") (class "Default")
      (node (ref "JP1") (pin "1") (pinfunction "1_1") (pintype "passive"))
    )
    (net (code "169") (name "unconnected-(JP1-Pad2)") (class "Default")
      (node (ref "JP1") (pin "2") (pinfunction "2_2") (pintype "passive"))
    )
    (net (code "170") (name "unconnected-(JP1-Pad3)") (class "Default")
      (node (ref "JP1") (pin "3") (pinfunction "3_3") (pintype "passive"))
    )
    (net (code "171") (name "unconnected-(JP1-Pad4)") (class "Default")
      (node (ref "JP1") (pin "4") (pinfunction "4_4") (pintype "passive"))
    )
    (net (code "172") (name "unconnected-(JP1-Pad5)") (class "Default")
      (node (ref "JP1") (pin "5") (pinfunction "5_5") (pintype "passive"))
    )
    (net (code "173") (name "unconnected-(JP1-Pad6)") (class "Default")
      (node (ref "JP1") (pin "6") (pinfunction "6_6") (pintype "passive"))
    )
    (net (code "174") (name "unconnected-(JP1-Pad7)") (class "Default")
      (node (ref "JP1") (pin "7") (pinfunction "7_7") (pintype "passive"))
    )
    (net (code "175") (name "unconnected-(JP1-Pad8)") (class "Default")
      (node (ref "JP1") (pin "8") (pinfunction "8_8") (pintype "passive"))
    )
    (net (code "176") (name "unconnected-(JP1-Pad9)") (class "Default")
      (node (ref "JP1") (pin "9") (pinfunction "9_9") (pintype "passive"))
    )
    (net (code "177") (name "unconnected-(JP1-Pad10)") (class "Default")
      (node (ref "JP1") (pin "10") (pinfunction "10_10") (pintype "passive"))
    )
    (net (code "178") (name "unconnected-(JP1-Pad11)") (class "Default")
      (node (ref "JP1") (pin "11") (pinfunction "11_11") (pintype "passive"))
    )
    (net (code "179") (name "unconnected-(JP1-Pad12)") (class "Default")
      (node (ref "JP1") (pin "12") (pinfunction "12_12") (pintype "passive"))
    )
    (net (code "180") (name "unconnected-(JP1-Pad13)") (class "Default")
      (node (ref "JP1") (pin "13") (pinfunction "13_13") (pintype "passive"))
    )
    (net (code "181") (name "unconnected-(JP1-Pad14)") (class "Default")
      (node (ref "JP1") (pin "14") (pinfunction "14_14") (pintype "passive"))
    )
    (net (code "182") (name "unconnected-(JP2-Pad1)") (class "Default")
      (node (ref "JP2") (pin "1") (pinfunction "1_1") (pintype "passive"))
    )
    (net (code "183") (name "unconnected-(JP2-Pad2)") (class "Default")
      (node (ref "JP2") (pin "2") (pinfunction "2_2") (pintype "passive"))
    )
    (net (code "184") (name "unconnected-(JP2-Pad3)") (class "Default")
      (node (ref "JP2") (pin "3") (pinfunction "3_3") (pintype "passive"))
    )
    (net (code "185") (name "unconnected-(JP2-Pad4)") (class "Default")
      (node (ref "JP2") (pin "4") (pinfunction "4_4") (pintype "passive"))
    )
    (net (code "186") (name "unconnected-(JP2-Pad5)") (class "Default")
      (node (ref "JP2") (pin "5") (pinfunction "5_5") (pintype "passive"))
    )
    (net (code "187") (name "unconnected-(JP2-Pad6)") (class "Default")
      (node (ref "JP2") (pin "6") (pinfunction "6_6") (pintype "passive"))
    )
    (net (code "188") (name "unconnected-(JP2-Pad7)") (class "Default")
      (node (ref "JP2") (pin "7") (pinfunction "7_7") (pintype "passive"))
    )
    (net (code "189") (name "unconnected-(JP2-Pad8)") (class "Default")
      (node (ref "JP2") (pin "8") (pinfunction "8_8") (pintype "passive"))
    )
    (net (code "190") (name "unconnected-(JP2-Pad9)") (class "Default")
      (node (ref "JP2") (pin "9") (pinfunction "9_9") (pintype "passive"))
    )
    (net (code "191") (name "unconnected-(JP2-Pad10)") (class "Default")
      (node (ref "JP2") (pin "10") (pinfunction "10_10") (pintype "passive"))
    )
    (net (code "192") (name "unconnected-(JP2-Pad11)") (class "Default")
      (node (ref "JP2") (pin "11") (pinfunction "11_11") (pintype "passive"))
    )
    (net (code "193") (name "unconnected-(JP2-Pad12)") (class "Default")
      (node (ref "JP2") (pin "12") (pinfunction "12_12") (pintype "passive"))
    )
    (net (code "194") (name "unconnected-(JP2-Pad13)") (class "Default")
      (node (ref "JP2") (pin "13") (pinfunction "13_13") (pintype "passive"))
    )
    (net (code "195") (name "unconnected-(JP2-Pad14)") (class "Default")
      (node (ref "JP2") (pin "14") (pinfunction "14_14") (pintype "passive"))
    )
  )
)
